# MB_DAC.net
KiCad netlist of a schematic drawn in Altium Designer
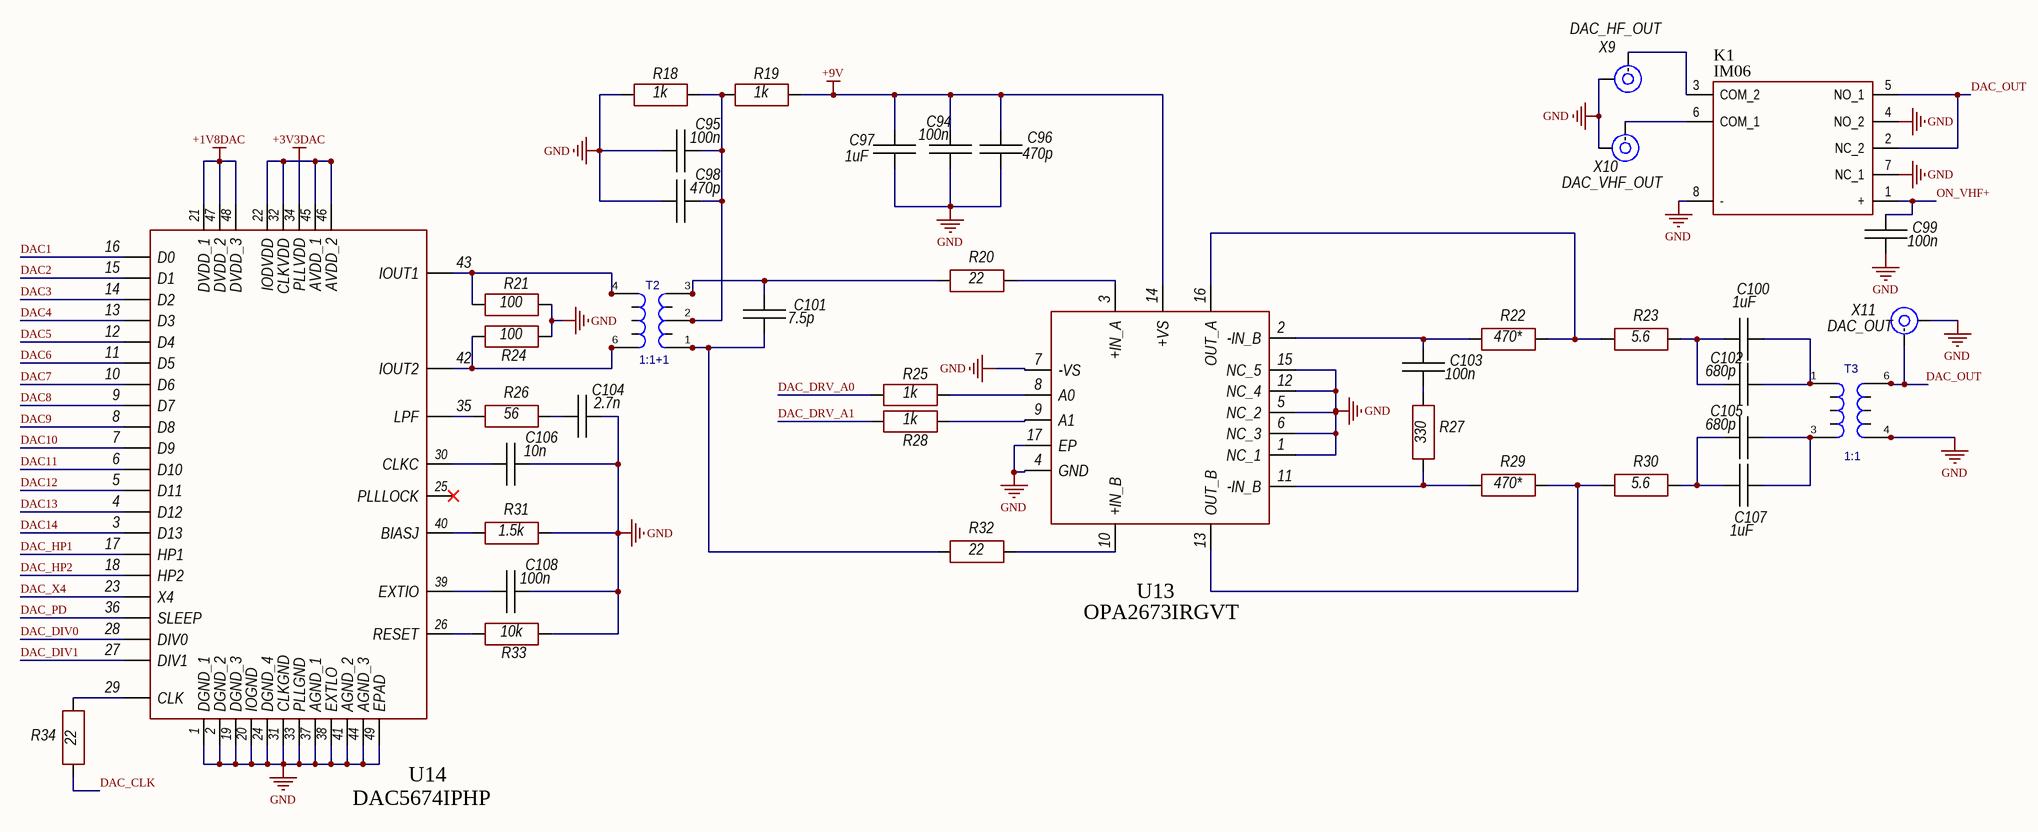
[diagram p0: MB_DAC.SchDoc]

(export (version "E")
  (design (tool "Eeschema 10.0.6"))
  (components
    (comp (ref "C94")
      (value "100n")
      (footprint "standard:CH0805C")
      (libsource (lib "Discrete") (part "Capacitor"))
    )
    (comp (ref "C95")
      (value "100n")
      (footprint "standard:CH0805C")
      (libsource (lib "Discrete") (part "Capacitor"))
    )
    (comp (ref "C96")
      (value "470p")
      (footprint "standard:CH0805C")
      (libsource (lib "Discrete") (part "Capacitor"))
    )
    (comp (ref "C97")
      (value "1uF")
      (footprint "standard:CH0805C")
      (libsource (lib "Discrete") (part "Capacitor"))
    )
    (comp (ref "C98")
      (value "470p")
      (footprint "standard:CH0805C")
      (libsource (lib "Discrete") (part "Capacitor"))
    )
    (comp (ref "C99")
      (value "100n")
      (footprint "standard:CH0805C")
      (libsource (lib "Discrete") (part "Capacitor"))
    )
    (comp (ref "C100")
      (value "1uF")
      (footprint "standard:CH0805C")
      (libsource (lib "Discrete") (part "Capacitor"))
    )
    (comp (ref "C101")
      (value "7.5p")
      (footprint "standard:CH0805C")
      (libsource (lib "Discrete") (part "Capacitor"))
    )
    (comp (ref "C102")
      (value "680p")
      (footprint "standard:CH0805C")
      (libsource (lib "Discrete") (part "Capacitor"))
    )
    (comp (ref "C103")
      (value "100n")
      (footprint "standard:CH0805C")
      (libsource (lib "Discrete") (part "Capacitor"))
    )
    (comp (ref "C104")
      (value "2.7n")
      (footprint "standard:CH0805C")
      (libsource (lib "Discrete") (part "Capacitor"))
    )
    (comp (ref "C105")
      (value "680p")
      (footprint "standard:CH0805C")
      (libsource (lib "Discrete") (part "Capacitor"))
    )
    (comp (ref "C106")
      (value "10n")
      (footprint "standard:CH0805C")
      (libsource (lib "Discrete") (part "Capacitor"))
    )
    (comp (ref "C107")
      (value "1uF")
      (footprint "standard:CH0805C")
      (libsource (lib "Discrete") (part "Capacitor"))
    )
    (comp (ref "C108")
      (value "100n")
      (footprint "standard:CH0805C")
      (libsource (lib "Discrete") (part "Capacitor"))
    )
    (comp (ref "K1") (value "IM06") (footprint "IM06") (libsource (lib "Relay") (part "IM06-V1")))
    (comp (ref "R18") (value "1k") (footprint "standard:CH0805R") (libsource (lib "") (part "Resistor_1")))
    (comp (ref "R19") (value "1k") (footprint "standard:CH0805R") (libsource (lib "") (part "Resistor_1")))
    (comp (ref "R20") (value "22") (footprint "standard:CH0805R") (libsource (lib "") (part "Resistor_1")))
    (comp (ref "R21") (value "100") (footprint "standard:CH0805R") (libsource (lib "") (part "Resistor_1")))
    (comp (ref "R22") (value "470*") (footprint "standard:CH0805R") (libsource (lib "") (part "Resistor_1")))
    (comp (ref "R23") (value "5.6") (footprint "standard:CH0805R") (libsource (lib "") (part "Resistor_1")))
    (comp (ref "R24") (value "100") (footprint "standard:CH0805R") (libsource (lib "") (part "Resistor_1")))
    (comp (ref "R25") (value "1k") (footprint "standard:CH0805R") (libsource (lib "") (part "Resistor_1")))
    (comp (ref "R26") (value "56") (footprint "standard:CH0805R") (libsource (lib "") (part "Resistor_1")))
    (comp (ref "R27")
      (value "330")
      (footprint "standard:CH0805R")
      (libsource (lib "Discrete") (part "Resistor"))
    )
    (comp (ref "R28") (value "1k") (footprint "standard:CH0805R") (libsource (lib "") (part "Resistor_1")))
    (comp (ref "R29") (value "470*") (footprint "standard:CH0805R") (libsource (lib "") (part "Resistor_1")))
    (comp (ref "R30") (value "5.6") (footprint "standard:CH0805R") (libsource (lib "") (part "Resistor_1")))
    (comp (ref "R31") (value "1.5k") (footprint "standard:CH0805R") (libsource (lib "") (part "Resistor_1")))
    (comp (ref "R32") (value "22") (footprint "standard:CH0805R") (libsource (lib "") (part "Resistor_1")))
    (comp (ref "R33") (value "10k") (footprint "standard:CH0805R") (libsource (lib "") (part "Resistor_1")))
    (comp (ref "R34")
      (value "22")
      (footprint "standard:CH0805R")
      (libsource (lib "Discrete") (part "Resistor"))
    )
    (comp (ref "T2")
      (value "1:1+1")
      (footprint "TRANSF_ACORE2")
      (description "Transformer")
      (libsource (lib "MOTHERBOARD_1") (part "TRANSF_ACORE2"))
    )
    (comp (ref "T3")
      (value "1:1")
      (footprint "TRANSF_ACORE")
      (description "Transformer")
      (libsource (lib "MOTHERBOARD_1") (part "TRANSF_ACORE"))
    )
    (comp (ref "U13")
      (value "OPA2673IRGVT")
      (footprint "16-QFN 4x4 PAD17")
      (libsource (lib "Digital") (part "OPA2673IRGVT"))
    )
    (comp (ref "U14")
      (value "DAC5674IPHP")
      (footprint "48-TQFP")
      (libsource (lib "Digital") (part "DAC5674IPHP"))
    )
    (comp (ref "X9")
      (value "DAC_HF_OUT")
      (footprint "custom:CON: SMA")
      (description "RF")
      (libsource (lib "Connectors") (part "SMA"))
    )
    (comp (ref "X10")
      (value "DAC_VHF_OUT")
      (footprint "custom:CON: SMA")
      (description "RF")
      (libsource (lib "Connectors") (part "SMA"))
    )
    (comp (ref "X11")
      (value "DAC_OUT")
      (footprint "custom:CON: SMA")
      (description "RF")
      (libsource (lib "Connectors") (part "SMA"))
    )
  )
  (nets
    (net (code "1") (name "+1V8DAC") (class "Default")
      (node (ref "U14") (pin "21") (pinfunction "DVDD_1_21") (pintype "power_in"))
      (node (ref "U14") (pin "47") (pinfunction "DVDD_2_47") (pintype "power_in"))
      (node (ref "U14") (pin "48") (pinfunction "DVDD_3_48") (pintype "power_in"))
    )
    (net (code "2") (name "+3V3DAC") (class "Default")
      (node (ref "U14") (pin "22") (pinfunction "IODVDD_22") (pintype "power_in"))
      (node (ref "U14") (pin "32") (pinfunction "CLKVDD_32") (pintype "power_in"))
      (node (ref "U14") (pin "34") (pinfunction "PLLVDD_34") (pintype "power_in"))
      (node (ref "U14") (pin "45") (pinfunction "AVDD_1_45") (pintype "power_in"))
      (node (ref "U14") (pin "46") (pinfunction "AVDD_2_46") (pintype "power_in"))
    )
    (net (code "3") (name "+9V") (class "Default")
      (node (ref "C94") (pin "2") (pinfunction "2_2") (pintype "power_in"))
      (node (ref "C96") (pin "2") (pinfunction "2_2") (pintype "power_in"))
      (node (ref "C97") (pin "2") (pinfunction "2_2") (pintype "power_in"))
      (node (ref "R19") (pin "1") (pinfunction "1_1") (pintype "passive"))
      (node (ref "U13") (pin "14") (pinfunction "+VS_14") (pintype "passive"))
    )
    (net (code "4") (name "/DAC1") (class "Default")
      (node (ref "U14") (pin "16") (pinfunction "D0_16") (pintype "power_in"))
    )
    (net (code "5") (name "/DAC2") (class "Default")
      (node (ref "U14") (pin "15") (pinfunction "D1_15") (pintype "power_in"))
    )
    (net (code "6") (name "/DAC3") (class "Default")
      (node (ref "U14") (pin "14") (pinfunction "D2_14") (pintype "power_in"))
    )
    (net (code "7") (name "/DAC4") (class "Default")
      (node (ref "U14") (pin "13") (pinfunction "D3_13") (pintype "power_in"))
    )
    (net (code "8") (name "/DAC5") (class "Default")
      (node (ref "U14") (pin "12") (pinfunction "D4_12") (pintype "power_in"))
    )
    (net (code "9") (name "/DAC6") (class "Default")
      (node (ref "U14") (pin "11") (pinfunction "D5_11") (pintype "power_in"))
    )
    (net (code "10") (name "/DAC7") (class "Default")
      (node (ref "U14") (pin "10") (pinfunction "D6_10") (pintype "power_in"))
    )
    (net (code "11") (name "/DAC8") (class "Default")
      (node (ref "U14") (pin "9") (pinfunction "D7_9") (pintype "power_in"))
    )
    (net (code "12") (name "/DAC9") (class "Default")
      (node (ref "U14") (pin "8") (pinfunction "D8_8") (pintype "power_in"))
    )
    (net (code "13") (name "/DAC10") (class "Default")
      (node (ref "U14") (pin "7") (pinfunction "D9_7") (pintype "power_in"))
    )
    (net (code "14") (name "/DAC11") (class "Default")
      (node (ref "U14") (pin "6") (pinfunction "D10_6") (pintype "power_in"))
    )
    (net (code "15") (name "/DAC12") (class "Default")
      (node (ref "U14") (pin "5") (pinfunction "D11_5") (pintype "power_in"))
    )
    (net (code "16") (name "/DAC13") (class "Default")
      (node (ref "U14") (pin "4") (pinfunction "D12_4") (pintype "power_in"))
    )
    (net (code "17") (name "/DAC14") (class "Default")
      (node (ref "U14") (pin "3") (pinfunction "D13_3") (pintype "power_in"))
    )
    (net (code "18") (name "/DAC_CLK") (class "Default")
      (node (ref "R34") (pin "2") (pinfunction "2_2") (pintype "passive"))
    )
    (net (code "19") (name "/DAC_DIV0") (class "Default")
      (node (ref "U14") (pin "28") (pinfunction "DIV0_28") (pintype "power_in"))
    )
    (net (code "20") (name "/DAC_DIV1") (class "Default")
      (node (ref "U14") (pin "27") (pinfunction "DIV1_27") (pintype "power_in"))
    )
    (net (code "21") (name "/DAC_DRV_A0") (class "Default")
      (node (ref "R25") (pin "2") (pinfunction "2_2") (pintype "passive"))
    )
    (net (code "22") (name "/DAC_DRV_A1") (class "Default")
      (node (ref "R28") (pin "2") (pinfunction "2_2") (pintype "passive"))
    )
    (net (code "23") (name "/DAC_HP1") (class "Default")
      (node (ref "U14") (pin "17") (pinfunction "HP1_17") (pintype "power_in"))
    )
    (net (code "24") (name "/DAC_HP2") (class "Default")
      (node (ref "U14") (pin "18") (pinfunction "HP2_18") (pintype "power_in"))
    )
    (net (code "25") (name "/DAC_OUT") (class "Default")
      (node (ref "K1") (pin "2") (pinfunction "NC_2_2") (pintype "passive"))
      (node (ref "K1") (pin "5") (pinfunction "NO_1_5") (pintype "passive"))
      (node (ref "T3") (pin "10") (pinfunction "0_10") (pintype "passive"))
      (node (ref "T3") (pin "6") (pinfunction "S1_6") (pintype "passive"))
      (node (ref "X11") (pin "1") (pinfunction "IN_1") (pintype "passive"))
    )
    (net (code "26") (name "/DAC_PD") (class "Default")
      (node (ref "U14") (pin "36") (pinfunction "SLEEP_36") (pintype "power_in"))
    )
    (net (code "27") (name "/DAC_X4") (class "Default")
      (node (ref "U14") (pin "23") (pinfunction "X4_23") (pintype "power_in"))
    )
    (net (code "28") (name "/ON_VHF+") (class "Default")
      (node (ref "C99") (pin "2") (pinfunction "2_2") (pintype "power_in"))
      (node (ref "K1") (pin "1") (pinfunction "+_1") (pintype "passive"))
    )
    (net (code "29") (name "GND") (class "Default")
      (node (ref "C104") (pin "2") (pinfunction "2_2") (pintype "power_in"))
      (node (ref "C106") (pin "2") (pinfunction "2_2") (pintype "power_in"))
      (node (ref "C108") (pin "2") (pinfunction "2_2") (pintype "power_in"))
      (node (ref "C94") (pin "1") (pinfunction "1_1") (pintype "power_in"))
      (node (ref "C95") (pin "1") (pinfunction "1_1") (pintype "power_in"))
      (node (ref "C96") (pin "1") (pinfunction "1_1") (pintype "power_in"))
      (node (ref "C97") (pin "1") (pinfunction "1_1") (pintype "power_in"))
      (node (ref "C98") (pin "1") (pinfunction "1_1") (pintype "power_in"))
      (node (ref "C99") (pin "1") (pinfunction "1_1") (pintype "power_in"))
      (node (ref "K1") (pin "4") (pinfunction "NO_2_4") (pintype "passive"))
      (node (ref "K1") (pin "7") (pinfunction "NC_1_7") (pintype "passive"))
      (node (ref "K1") (pin "8") (pinfunction "-_8") (pintype "passive"))
      (node (ref "R18") (pin "2") (pinfunction "2_2") (pintype "passive"))
      (node (ref "R21") (pin "1") (pinfunction "1_1") (pintype "passive"))
      (node (ref "R24") (pin "1") (pinfunction "1_1") (pintype "passive"))
      (node (ref "R31") (pin "1") (pinfunction "1_1") (pintype "passive"))
      (node (ref "R33") (pin "1") (pinfunction "1_1") (pintype "passive"))
      (node (ref "T3") (pin "11") (pinfunction "0_11") (pintype "passive"))
      (node (ref "T3") (pin "4") (pinfunction "S2_4") (pintype "passive"))
      (node (ref "U13") (pin "1") (pinfunction "NC_1_1") (pintype "passive"))
      (node (ref "U13") (pin "12") (pinfunction "NC_4_12") (pintype "passive"))
      (node (ref "U13") (pin "15") (pinfunction "NC_5_15") (pintype "passive"))
      (node (ref "U13") (pin "17") (pinfunction "EP_17") (pintype "passive"))
      (node (ref "U13") (pin "4") (pinfunction "GND_4") (pintype "passive"))
      (node (ref "U13") (pin "5") (pinfunction "NC_2_5") (pintype "passive"))
      (node (ref "U13") (pin "6") (pinfunction "NC_3_6") (pintype "passive"))
      (node (ref "U13") (pin "7") (pinfunction "-VS_7") (pintype "passive"))
      (node (ref "U14") (pin "1") (pinfunction "DGND_1_1") (pintype "power_in"))
      (node (ref "U14") (pin "19") (pinfunction "DGND_3_19") (pintype "power_in"))
      (node (ref "U14") (pin "2") (pinfunction "DGND_2_2") (pintype "power_in"))
      (node (ref "U14") (pin "20") (pinfunction "IOGND_20") (pintype "power_in"))
      (node (ref "U14") (pin "24") (pinfunction "DGND_4_24") (pintype "power_in"))
      (node (ref "U14") (pin "31") (pinfunction "CLKGND_31") (pintype "power_in"))
      (node (ref "U14") (pin "33") (pinfunction "PLLGND_33") (pintype "power_in"))
      (node (ref "U14") (pin "37") (pinfunction "AGND_1_37") (pintype "power_in"))
      (node (ref "U14") (pin "38") (pinfunction "EXTLO_38") (pintype "power_in"))
      (node (ref "U14") (pin "41") (pinfunction "AGND_2_41") (pintype "power_in"))
      (node (ref "U14") (pin "44") (pinfunction "AGND_3_44") (pintype "power_in"))
      (node (ref "U14") (pin "49") (pinfunction "EPAD_49") (pintype "power_in"))
      (node (ref "X10") (pin "2") (pinfunction "IN_2") (pintype "passive"))
      (node (ref "X11") (pin "2") (pinfunction "IN_2") (pintype "passive"))
      (node (ref "X9") (pin "2") (pinfunction "IN_2") (pintype "passive"))
    )
    (net (code "30") (name "Net-(C100-Pad2)") (class "Default")
      (node (ref "C100") (pin "2") (pinfunction "2_2") (pintype "power_in"))
      (node (ref "C102") (pin "2") (pinfunction "2_2") (pintype "power_in"))
      (node (ref "R23") (pin "1") (pinfunction "1_1") (pintype "passive"))
    )
    (net (code "31") (name "Net-(C103-Pad1)") (class "Default")
      (node (ref "C103") (pin "1") (pinfunction "1_1") (pintype "power_in"))
      (node (ref "R27") (pin "1") (pinfunction "1_1") (pintype "passive"))
    )
    (net (code "32") (name "Net-(C103-Pad2)") (class "Default")
      (node (ref "C103") (pin "2") (pinfunction "2_2") (pintype "power_in"))
      (node (ref "R22") (pin "2") (pinfunction "2_2") (pintype "passive"))
      (node (ref "U13") (pin "2") (pinfunction "-IN_B_2") (pintype "passive"))
    )
    (net (code "33") (name "Net-(C104-Pad1)") (class "Default")
      (node (ref "C104") (pin "1") (pinfunction "1_1") (pintype "power_in"))
      (node (ref "R26") (pin "1") (pinfunction "1_1") (pintype "passive"))
    )
    (net (code "34") (name "Net-(C105-Pad2)") (class "Default")
      (node (ref "C105") (pin "2") (pinfunction "2_2") (pintype "power_in"))
      (node (ref "C107") (pin "2") (pinfunction "2_2") (pintype "power_in"))
      (node (ref "R30") (pin "1") (pinfunction "1_1") (pintype "passive"))
    )
    (net (code "35") (name "Net-(K1-COM_1)") (class "Default")
      (node (ref "K1") (pin "6") (pinfunction "COM_1_6") (pintype "passive"))
      (node (ref "X10") (pin "1") (pinfunction "IN_1") (pintype "passive"))
    )
    (net (code "36") (name "Net-(K1-COM_2)") (class "Default")
      (node (ref "K1") (pin "3") (pinfunction "COM_2_3") (pintype "passive"))
      (node (ref "X9") (pin "1") (pinfunction "IN_1") (pintype "passive"))
    )
    (net (code "37") (name "Net-(R27-Pad2)") (class "Default")
      (node (ref "R27") (pin "2") (pinfunction "2_2") (pintype "passive"))
      (node (ref "R29") (pin "2") (pinfunction "2_2") (pintype "passive"))
      (node (ref "U13") (pin "11") (pinfunction "-IN_B_11") (pintype "passive"))
    )
    (net (code "38") (name "Net-(T2-P1)") (class "Default")
      (node (ref "R21") (pin "2") (pinfunction "2_2") (pintype "passive"))
      (node (ref "T2") (pin "11") (pinfunction "0_11") (pintype "passive"))
      (node (ref "T2") (pin "4") (pinfunction "P1_4") (pintype "passive"))
      (node (ref "U14") (pin "43") (pinfunction "IOUT1_43") (pintype "passive"))
    )
    (net (code "39") (name "Net-(T2-P2)") (class "Default")
      (node (ref "R24") (pin "2") (pinfunction "2_2") (pintype "passive"))
      (node (ref "T2") (pin "10") (pinfunction "0_10") (pintype "passive"))
      (node (ref "T2") (pin "6") (pinfunction "P2_6") (pintype "passive"))
      (node (ref "U14") (pin "42") (pinfunction "IOUT2_42") (pintype "passive"))
    )
    (net (code "40") (name "Net-(T2-S1)") (class "Default")
      (node (ref "C101") (pin "1") (pinfunction "1_1") (pintype "power_in"))
      (node (ref "R20") (pin "2") (pinfunction "2_2") (pintype "passive"))
      (node (ref "T2") (pin "3") (pinfunction "S1_3") (pintype "passive"))
      (node (ref "T2") (pin "9") (pinfunction "0_9") (pintype "passive"))
    )
    (net (code "41") (name "Net-(T2-S2)") (class "Default")
      (node (ref "C95") (pin "2") (pinfunction "2_2") (pintype "power_in"))
      (node (ref "C98") (pin "2") (pinfunction "2_2") (pintype "power_in"))
      (node (ref "R18") (pin "1") (pinfunction "1_1") (pintype "passive"))
      (node (ref "R19") (pin "2") (pinfunction "2_2") (pintype "passive"))
      (node (ref "T2") (pin "2") (pinfunction "S2_2") (pintype "passive"))
      (node (ref "T2") (pin "8") (pinfunction "0_8") (pintype "passive"))
    )
    (net (code "42") (name "Net-(T2-S3)") (class "Default")
      (node (ref "C101") (pin "2") (pinfunction "2_2") (pintype "power_in"))
      (node (ref "R32") (pin "2") (pinfunction "2_2") (pintype "passive"))
      (node (ref "T2") (pin "1") (pinfunction "S3_1") (pintype "passive"))
      (node (ref "T2") (pin "7") (pinfunction "0_7") (pintype "passive"))
    )
    (net (code "43") (name "Net-(T3-P1)") (class "Default")
      (node (ref "C100") (pin "1") (pinfunction "1_1") (pintype "power_in"))
      (node (ref "C102") (pin "1") (pinfunction "1_1") (pintype "power_in"))
      (node (ref "T3") (pin "1") (pinfunction "P1_1") (pintype "passive"))
      (node (ref "T3") (pin "7") (pinfunction "0_7") (pintype "passive"))
    )
    (net (code "44") (name "Net-(T3-P2)") (class "Default")
      (node (ref "C105") (pin "1") (pinfunction "1_1") (pintype "power_in"))
      (node (ref "C107") (pin "1") (pinfunction "1_1") (pintype "power_in"))
      (node (ref "T3") (pin "3") (pinfunction "P2_3") (pintype "passive"))
      (node (ref "T3") (pin "9") (pinfunction "0_9") (pintype "passive"))
    )
    (net (code "45") (name "Net-(U13-+IN_A)") (class "Default")
      (node (ref "R20") (pin "1") (pinfunction "1_1") (pintype "passive"))
      (node (ref "U13") (pin "3") (pinfunction "+IN_A_3") (pintype "passive"))
    )
    (net (code "46") (name "Net-(U13-+IN_B)") (class "Default")
      (node (ref "R32") (pin "1") (pinfunction "1_1") (pintype "passive"))
      (node (ref "U13") (pin "10") (pinfunction "+IN_B_10") (pintype "passive"))
    )
    (net (code "47") (name "Net-(U13-A0)") (class "Default")
      (node (ref "R25") (pin "1") (pinfunction "1_1") (pintype "passive"))
      (node (ref "U13") (pin "8") (pinfunction "A0_8") (pintype "passive"))
    )
    (net (code "48") (name "Net-(U13-A1)") (class "Default")
      (node (ref "R28") (pin "1") (pinfunction "1_1") (pintype "passive"))
      (node (ref "U13") (pin "9") (pinfunction "A1_9") (pintype "passive"))
    )
    (net (code "49") (name "Net-(U13-OUT_A)") (class "Default")
      (node (ref "R22") (pin "1") (pinfunction "1_1") (pintype "passive"))
      (node (ref "R23") (pin "2") (pinfunction "2_2") (pintype "passive"))
      (node (ref "U13") (pin "16") (pinfunction "OUT_A_16") (pintype "passive"))
    )
    (net (code "50") (name "Net-(U13-OUT_B)") (class "Default")
      (node (ref "R29") (pin "1") (pinfunction "1_1") (pintype "passive"))
      (node (ref "R30") (pin "2") (pinfunction "2_2") (pintype "passive"))
      (node (ref "U13") (pin "13") (pinfunction "OUT_B_13") (pintype "passive"))
    )
    (net (code "51") (name "Net-(U14-BIASJ)") (class "Default")
      (node (ref "R31") (pin "2") (pinfunction "2_2") (pintype "passive"))
      (node (ref "U14") (pin "40") (pinfunction "BIASJ_40") (pintype "power_in"))
    )
    (net (code "52") (name "Net-(U14-CLK)") (class "Default")
      (node (ref "R34") (pin "1") (pinfunction "1_1") (pintype "passive"))
      (node (ref "U14") (pin "29") (pinfunction "CLK_29") (pintype "power_in"))
    )
    (net (code "53") (name "Net-(U14-CLKC)") (class "Default")
      (node (ref "C106") (pin "1") (pinfunction "1_1") (pintype "power_in"))
      (node (ref "U14") (pin "30") (pinfunction "CLKC_30") (pintype "power_in"))
    )
    (net (code "54") (name "Net-(U14-EXTIO)") (class "Default")
      (node (ref "C108") (pin "1") (pinfunction "1_1") (pintype "power_in"))
      (node (ref "U14") (pin "39") (pinfunction "EXTIO_39") (pintype "power_in"))
    )
    (net (code "55") (name "Net-(U14-LPF)") (class "Default")
      (node (ref "R26") (pin "2") (pinfunction "2_2") (pintype "passive"))
      (node (ref "U14") (pin "35") (pinfunction "LPF_35") (pintype "passive"))
    )
    (net (code "56") (name "Net-(U14-RESET)") (class "Default")
      (node (ref "R33") (pin "2") (pinfunction "2_2") (pintype "passive"))
      (node (ref "U14") (pin "26") (pinfunction "RESET_26") (pintype "power_in"))
    )
    (net (code "57") (name "unconnected-(T3-0-Pad8)") (class "Default")
      (node (ref "T3") (pin "8") (pinfunction "0_8") (pintype "passive"))
    )
    (net (code "58") (name "unconnected-(U14-PLLLOCK-Pad25)") (class "Default")
      (node (ref "U14") (pin "25") (pinfunction "PLLLOCK_25") (pintype "power_in+no_connect"))
    )
  )
)
